# Deel_1_ATMEGA.net
KiCad netlist of a schematic drawn in Altium Designer
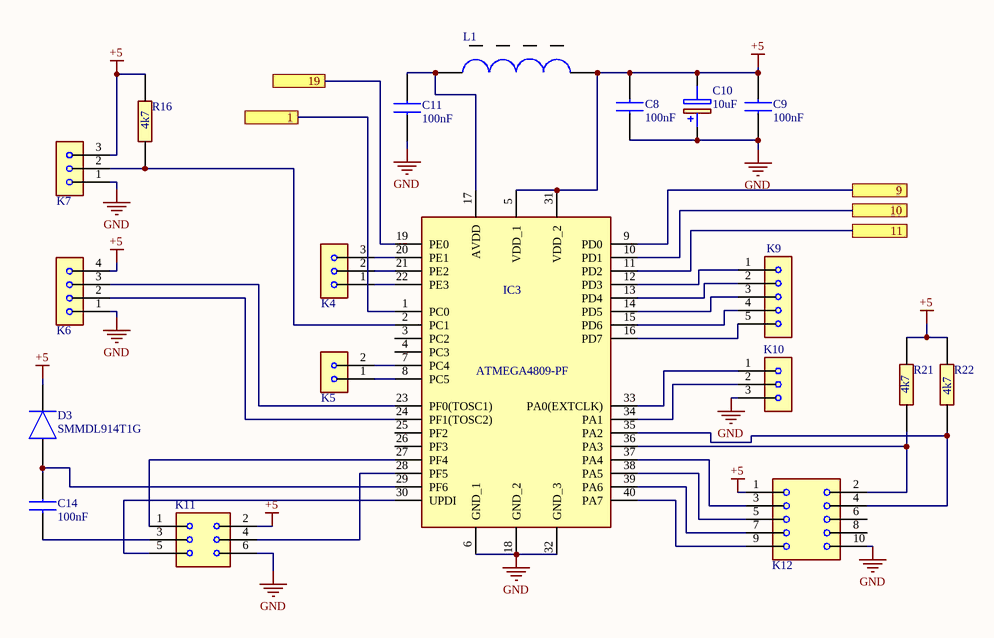
[diagram p0: Deel_1_ATMEGA.SchDoc]

(export (version "E")
  (design (tool "Eeschema 10.0.6"))
  (components
    (comp (ref "C8")
      (value "100nF")
      (footprint "PcbLib1:100nF")
      (description "Capacitor")
      (fields
        (field (name "MANUFACTURER_PART_NUMBER") "0402YC104MAT2A")
        (field (name "MOUSER PART NUMBER") "581-0402YC104MAT2A")
      )
      (libsource (lib "Schlib_soldeerstation") (part "100nF"))
    )
    (comp (ref "C9")
      (value "100nF")
      (footprint "PcbLib1:100nF")
      (description "Capacitor")
      (fields
        (field (name "MANUFACTURER_PART_NUMBER") "0402YC104MAT2A")
        (field (name "MOUSER PART NUMBER") "581-0402YC104MAT2A")
      )
      (libsource (lib "Schlib_soldeerstation") (part "100nF"))
    )
    (comp (ref "C10")
      (value "10uF")
      (footprint "PcbLib1:10uf")
      (description "Capacitor Polarised 860020672010")
      (fields
        (field (name "MOUSER2 PART NUMBER") "710-860020672010")
        (field (name "MANUFACTURER_PART_NUMBER") "860020672010")
      )
      (libsource (lib "Schlib_soldeerstation") (part "10uF"))
    )
    (comp (ref "C11")
      (value "100nF")
      (footprint "PcbLib1:100nF")
      (description "Capacitor")
      (fields
        (field (name "MANUFACTURER_PART_NUMBER") "0402YC104MAT2A")
        (field (name "MOUSER PART NUMBER") "581-0402YC104MAT2A")
      )
      (libsource (lib "Schlib_soldeerstation") (part "100nF"))
    )
    (comp (ref "C14")
      (value "100nF")
      (footprint "PcbLib1:100nF")
      (description "Capacitor")
      (fields
        (field (name "MANUFACTURER_PART_NUMBER") "0402YC104MAT2A")
        (field (name "MOUSER PART NUMBER") "581-0402YC104MAT2A")
      )
      (libsource (lib "Schlib_soldeerstation") (part "100nF"))
    )
    (comp (ref "D3")
      (value "SMMDL914T1G")
      (footprint "PcbLib1:smmdl914")
      (description "Diode SMMDL914T1G")
      (fields (field (name "MOUSER2 PART NUMBER") "863-SMMDL914T1G"))
      (libsource (lib "Schlib_soldeerstation") (part "SMMDL914T1G"))
    )
    (comp (ref "IC3")
      (value "ATMEGA4809-PF")
      (footprint "PcbLib1:ATMEGA4809-PF")
      (description "Integrated Circuit")
      (fields (field (name "MOUSER PART NUMBER") "556-ATMEGA4809-PF"))
      (libsource (lib "Schlib_soldeerstation") (part "ATMEGA4809-PF"))
    )
    (comp (ref "K4")
      (value "1x3header")
      (footprint "PcbLib1:HDR1X3")
      (description "Connector")
      (fields (field (name "MANUFACTURER_PART_NUMBER") "0022035035"))
      (libsource (lib "") (part "1x3header_1"))
    )
    (comp (ref "K5")
      (value "1x2header")
      (footprint "PcbLib1:HDR1X2")
      (description "Connector")
      (fields (field (name "MANUFACTURER_PART_NUMBER") "0022232021"))
      (libsource (lib "Schlib_soldeerstation") (part "1x2header"))
    )
    (comp (ref "K6")
      (value "1x4header")
      (footprint "PcbLib1:HDR1X4")
      (description "Connector")
      (fields (field (name "MANUFACTURER_PART_NUMBER") "0009652048"))
      (libsource (lib "Schlib_soldeerstation") (part "1x4header"))
    )
    (comp (ref "K7")
      (value "1x3header")
      (footprint "PcbLib1:HDR1X3")
      (description "Connector")
      (fields (field (name "MANUFACTURER_PART_NUMBER") "0022035035"))
      (libsource (lib "") (part "1x3header_1"))
    )
    (comp (ref "K9")
      (value "1x5header")
      (footprint "PcbLib1:HDR1X5")
      (description "Connector")
      (fields (field (name "MANUFACTURER_PART_NUMBER") "0353620550"))
      (libsource (lib "Schlib_soldeerstation") (part "1x5header"))
    )
    (comp (ref "K10")
      (value "1x3header")
      (footprint "PcbLib1:HDR1X3")
      (description "Connector")
      (fields (field (name "MANUFACTURER_PART_NUMBER") "0022035035"))
      (libsource (lib "Schlib_soldeerstation") (part "1x3header"))
    )
    (comp (ref "K11")
      (value "2x3header")
      (footprint "PcbLib1:HDR2X3")
      (description "Connector")
      (fields
        (field (name "MANUFACTURER_PART_NUMBER") "10129381-906002BLF")
        (field (name "MOUSER PART NUMBER") "649-1012938190602BLF")
      )
      (libsource (lib "Schlib_soldeerstation") (part "2x3header"))
    )
    (comp (ref "K12")
      (value "10 boxheader")
      (footprint "PcbLib1:10BoxHeader")
      (description "Connector")
      (fields (field (name "MANUFACTURER_PART_NUMBER") "0010897100"))
      (libsource (lib "Schlib_soldeerstation") (part "10 boxheader"))
    )
    (comp (ref "L1")
      (value "smoorspoel")
      (footprint "PcbLib1:smoorspoel")
      (description "Inductor VLS6045EX-100M-H")
      (fields
        (field (name "MOUSER2 PART NUMBER") "810-VLS6045EX-100M-H")
        (field (name "MANUFACTURER_PART_NUMBER") "VLS6045EX-100M-H")
      )
      (libsource (lib "Schlib_soldeerstation") (part "smoorspoel"))
    )
    (comp (ref "R16")
      (value "4k7")
      (footprint "PcbLib1:4k7")
      (description "Resistor")
      (fields
        (field (name "MANUFACTURER_PART_NUMBER") "CPF0805B100RE1")
        (field (name "MOUSER PART NUMBER") "279-CPF0805B100RE1")
      )
      (libsource (lib "Schlib_soldeerstation") (part "4k7"))
    )
    (comp (ref "R21")
      (value "4k7")
      (footprint "PcbLib1:4k7")
      (description "Resistor")
      (fields
        (field (name "MANUFACTURER_PART_NUMBER") "CPF0805B100RE1")
        (field (name "MOUSER PART NUMBER") "279-CPF0805B100RE1")
      )
      (libsource (lib "Schlib_soldeerstation") (part "4k7"))
    )
    (comp (ref "R22")
      (value "4k7")
      (footprint "PcbLib1:4k7")
      (description "Resistor")
      (fields
        (field (name "MANUFACTURER_PART_NUMBER") "CPF0805B100RE1")
        (field (name "MOUSER PART NUMBER") "279-CPF0805B100RE1")
      )
      (libsource (lib "Schlib_soldeerstation") (part "4k7"))
    )
  )
  (nets
    (net (code "1") (name "+5") (class "Default")
      (node (ref "C10") (pin "2") (pinfunction "-_2") (pintype "passive"))
      (node (ref "C8") (pin "2") (pinfunction "2_2") (pintype "passive"))
      (node (ref "C9") (pin "2") (pinfunction "2_2") (pintype "passive"))
      (node (ref "D3") (pin "1") (pinfunction "K_1") (pintype "passive"))
      (node (ref "IC3") (pin "31") (pinfunction "VDD_2_31") (pintype "passive"))
      (node (ref "IC3") (pin "5") (pinfunction "VDD_1_5") (pintype "passive"))
      (node (ref "K11") (pin "2") (pinfunction "2_2") (pintype "passive"))
      (node (ref "K12") (pin "1") (pinfunction "1_1") (pintype "passive"))
      (node (ref "K6") (pin "4") (pinfunction "4_4") (pintype "passive"))
      (node (ref "K7") (pin "3") (pinfunction "3_3") (pintype "passive"))
      (node (ref "L1") (pin "2") (pinfunction "2_2") (pintype "passive"))
      (node (ref "R16") (pin "2") (pinfunction "2_2") (pintype "passive"))
      (node (ref "R21") (pin "2") (pinfunction "2_2") (pintype "passive"))
      (node (ref "R22") (pin "2") (pinfunction "2_2") (pintype "passive"))
    )
    (net (code "2") (name "/1") (class "Default")
      (node (ref "IC3") (pin "1") (pinfunction "PC0_1") (pintype "passive"))
    )
    (net (code "3") (name "/9") (class "Default")
      (node (ref "IC3") (pin "9") (pinfunction "PD0_9") (pintype "passive"))
    )
    (net (code "4") (name "/10") (class "Default")
      (node (ref "IC3") (pin "10") (pinfunction "PD1_10") (pintype "passive"))
    )
    (net (code "5") (name "/11") (class "Default")
      (node (ref "IC3") (pin "11") (pinfunction "PD2_11") (pintype "passive"))
    )
    (net (code "6") (name "/19") (class "Default")
      (node (ref "IC3") (pin "19") (pinfunction "PE0_19") (pintype "passive"))
    )
    (net (code "7") (name "GND") (class "Default")
      (node (ref "C10") (pin "1") (pinfunction "+_1") (pintype "passive"))
      (node (ref "C11") (pin "1") (pinfunction "1_1") (pintype "passive"))
      (node (ref "C8") (pin "1") (pinfunction "1_1") (pintype "passive"))
      (node (ref "C9") (pin "1") (pinfunction "1_1") (pintype "passive"))
      (node (ref "IC3") (pin "18") (pinfunction "GND_2_18") (pintype "passive"))
      (node (ref "IC3") (pin "32") (pinfunction "GND_3_32") (pintype "passive"))
      (node (ref "IC3") (pin "6") (pinfunction "GND_1_6") (pintype "passive"))
      (node (ref "K10") (pin "3") (pinfunction "3_3") (pintype "passive"))
      (node (ref "K11") (pin "6") (pinfunction "6_6") (pintype "passive"))
      (node (ref "K12") (pin "10") (pinfunction "10_10") (pintype "passive"))
      (node (ref "K6") (pin "1") (pinfunction "1_1") (pintype "passive"))
      (node (ref "K7") (pin "1") (pinfunction "1_1") (pintype "passive"))
    )
    (net (code "8") (name "Net-(C14-Pad1)") (class "Default")
      (node (ref "C14") (pin "1") (pinfunction "1_1") (pintype "passive"))
      (node (ref "K11") (pin "3") (pinfunction "3_3") (pintype "passive"))
    )
    (net (code "9") (name "Net-(D3-A)") (class "Default")
      (node (ref "C14") (pin "2") (pinfunction "2_2") (pintype "passive"))
      (node (ref "D3") (pin "2") (pinfunction "A_2") (pintype "passive"))
      (node (ref "IC3") (pin "29") (pinfunction "PF6_29") (pintype "passive"))
    )
    (net (code "10") (name "Net-(IC3-AVDD)") (class "Default")
      (node (ref "C11") (pin "2") (pinfunction "2_2") (pintype "passive"))
      (node (ref "IC3") (pin "17") (pinfunction "AVDD_17") (pintype "passive"))
      (node (ref "L1") (pin "1") (pinfunction "1_1") (pintype "passive"))
    )
    (net (code "11") (name "Net-(IC3-PA0(EXTCLK))") (class "Default")
      (node (ref "IC3") (pin "33") (pinfunction "PA0(EXTCLK)_33") (pintype "passive"))
      (node (ref "K10") (pin "1") (pinfunction "1_1") (pintype "passive"))
    )
    (net (code "12") (name "Net-(IC3-PA1)") (class "Default")
      (node (ref "IC3") (pin "34") (pinfunction "PA1_34") (pintype "passive"))
      (node (ref "K10") (pin "2") (pinfunction "2_2") (pintype "passive"))
    )
    (net (code "13") (name "Net-(IC3-PA2)") (class "Default")
      (node (ref "IC3") (pin "35") (pinfunction "PA2_35") (pintype "passive"))
      (node (ref "K12") (pin "4") (pinfunction "4_4") (pintype "passive"))
      (node (ref "R22") (pin "1") (pinfunction "1_1") (pintype "passive"))
    )
    (net (code "14") (name "Net-(IC3-PA3)") (class "Default")
      (node (ref "IC3") (pin "36") (pinfunction "PA3_36") (pintype "passive"))
      (node (ref "K12") (pin "2") (pinfunction "2_2") (pintype "passive"))
      (node (ref "R21") (pin "1") (pinfunction "1_1") (pintype "passive"))
    )
    (net (code "15") (name "Net-(IC3-PA4)") (class "Default")
      (node (ref "IC3") (pin "37") (pinfunction "PA4_37") (pintype "passive"))
      (node (ref "K12") (pin "3") (pinfunction "3_3") (pintype "passive"))
    )
    (net (code "16") (name "Net-(IC3-PA5)") (class "Default")
      (node (ref "IC3") (pin "38") (pinfunction "PA5_38") (pintype "passive"))
      (node (ref "K12") (pin "5") (pinfunction "5_5") (pintype "passive"))
    )
    (net (code "17") (name "Net-(IC3-PA6)") (class "Default")
      (node (ref "IC3") (pin "39") (pinfunction "PA6_39") (pintype "passive"))
      (node (ref "K12") (pin "7") (pinfunction "7_7") (pintype "passive"))
    )
    (net (code "18") (name "Net-(IC3-PA7)") (class "Default")
      (node (ref "IC3") (pin "40") (pinfunction "PA7_40") (pintype "passive"))
      (node (ref "K12") (pin "9") (pinfunction "9_9") (pintype "passive"))
    )
    (net (code "19") (name "Net-(IC3-PC1)") (class "Default")
      (node (ref "IC3") (pin "2") (pinfunction "PC1_2") (pintype "passive"))
      (node (ref "K7") (pin "2") (pinfunction "2_2") (pintype "passive"))
      (node (ref "R16") (pin "1") (pinfunction "1_1") (pintype "passive"))
    )
    (net (code "20") (name "Net-(IC3-PC4)") (class "Default")
      (node (ref "IC3") (pin "7") (pinfunction "PC4_7") (pintype "passive"))
      (node (ref "K5") (pin "2") (pinfunction "2_2") (pintype "passive"))
    )
    (net (code "21") (name "Net-(IC3-PC5)") (class "Default")
      (node (ref "IC3") (pin "8") (pinfunction "PC5_8") (pintype "passive"))
      (node (ref "K5") (pin "1") (pinfunction "1_1") (pintype "passive"))
    )
    (net (code "22") (name "Net-(IC3-PD3)") (class "Default")
      (node (ref "IC3") (pin "12") (pinfunction "PD3_12") (pintype "passive"))
      (node (ref "K9") (pin "1") (pinfunction "1_1") (pintype "passive"))
    )
    (net (code "23") (name "Net-(IC3-PD4)") (class "Default")
      (node (ref "IC3") (pin "13") (pinfunction "PD4_13") (pintype "passive"))
      (node (ref "K9") (pin "2") (pinfunction "2_2") (pintype "passive"))
    )
    (net (code "24") (name "Net-(IC3-PD5)") (class "Default")
      (node (ref "IC3") (pin "14") (pinfunction "PD5_14") (pintype "passive"))
      (node (ref "K9") (pin "3") (pinfunction "3_3") (pintype "passive"))
    )
    (net (code "25") (name "Net-(IC3-PD6)") (class "Default")
      (node (ref "IC3") (pin "15") (pinfunction "PD6_15") (pintype "passive"))
      (node (ref "K9") (pin "4") (pinfunction "4_4") (pintype "passive"))
    )
    (net (code "26") (name "Net-(IC3-PD7)") (class "Default")
      (node (ref "IC3") (pin "16") (pinfunction "PD7_16") (pintype "passive"))
      (node (ref "K9") (pin "5") (pinfunction "5_5") (pintype "passive"))
    )
    (net (code "27") (name "Net-(IC3-PE1)") (class "Default")
      (node (ref "IC3") (pin "20") (pinfunction "PE1_20") (pintype "passive"))
      (node (ref "K4") (pin "3") (pinfunction "3_3") (pintype "passive"))
    )
    (net (code "28") (name "Net-(IC3-PE2)") (class "Default")
      (node (ref "IC3") (pin "21") (pinfunction "PE2_21") (pintype "passive"))
      (node (ref "K4") (pin "2") (pinfunction "2_2") (pintype "passive"))
    )
    (net (code "29") (name "Net-(IC3-PE3)") (class "Default")
      (node (ref "IC3") (pin "22") (pinfunction "PE3_22") (pintype "passive"))
      (node (ref "K4") (pin "1") (pinfunction "1_1") (pintype "passive"))
    )
    (net (code "30") (name "Net-(IC3-PF0(TOSC1))") (class "Default")
      (node (ref "IC3") (pin "23") (pinfunction "PF0(TOSC1)_23") (pintype "passive"))
      (node (ref "K6") (pin "3") (pinfunction "3_3") (pintype "passive"))
    )
    (net (code "31") (name "Net-(IC3-PF1(TOSC2))") (class "Default")
      (node (ref "IC3") (pin "24") (pinfunction "PF1(TOSC2)_24") (pintype "passive"))
      (node (ref "K6") (pin "2") (pinfunction "2_2") (pintype "passive"))
    )
    (net (code "32") (name "Net-(IC3-PF4)") (class "Default")
      (node (ref "IC3") (pin "27") (pinfunction "PF4_27") (pintype "passive"))
      (node (ref "K11") (pin "1") (pinfunction "1_1") (pintype "passive"))
    )
    (net (code "33") (name "Net-(IC3-PF5)") (class "Default")
      (node (ref "IC3") (pin "28") (pinfunction "PF5_28") (pintype "passive"))
      (node (ref "K11") (pin "4") (pinfunction "4_4") (pintype "passive"))
    )
    (net (code "34") (name "Net-(IC3-UPDI)") (class "Default")
      (node (ref "IC3") (pin "30") (pinfunction "UPDI_30") (pintype "passive"))
      (node (ref "K11") (pin "5") (pinfunction "5_5") (pintype "passive"))
    )
    (net (code "35") (name "unconnected-(IC3-PC2-Pad3)") (class "Default")
      (node (ref "IC3") (pin "3") (pinfunction "PC2_3") (pintype "passive"))
    )
    (net (code "36") (name "unconnected-(IC3-PC3-Pad4)") (class "Default")
      (node (ref "IC3") (pin "4") (pinfunction "PC3_4") (pintype "passive"))
    )
    (net (code "37") (name "unconnected-(IC3-PF2-Pad25)") (class "Default")
      (node (ref "IC3") (pin "25") (pinfunction "PF2_25") (pintype "passive"))
    )
    (net (code "38") (name "unconnected-(IC3-PF3-Pad26)") (class "Default")
      (node (ref "IC3") (pin "26") (pinfunction "PF3_26") (pintype "passive"))
    )
    (net (code "39") (name "unconnected-(K12-Pad6)") (class "Default")
      (node (ref "K12") (pin "6") (pinfunction "6_6") (pintype "passive"))
    )
    (net (code "40") (name "unconnected-(K12-Pad8)") (class "Default")
      (node (ref "K12") (pin "8") (pinfunction "8_8") (pintype "passive"))
    )
  )
)
